# RTC_IC.net
KiCad netlist of a schematic drawn in Altium Designer
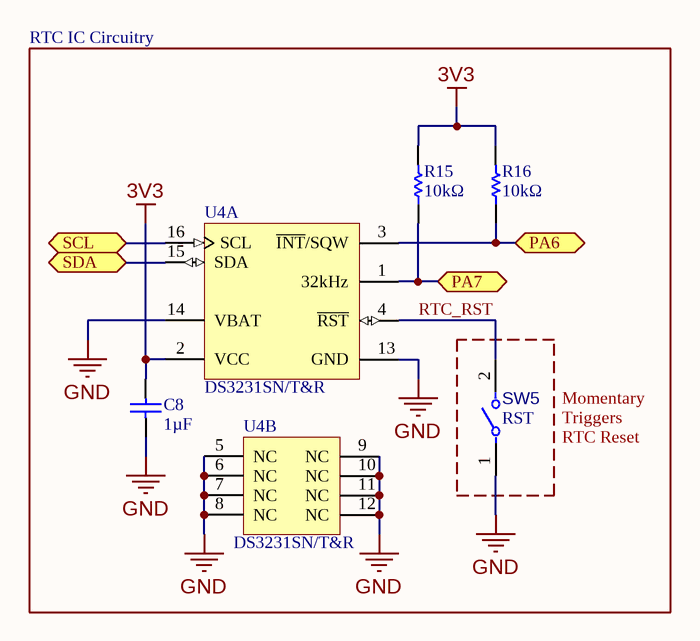
[diagram p0: RTC IC.SchDoc]

(export (version "E")
  (design (tool "Eeschema 10.0.6"))
  (components
    (comp (ref "C8")
      (value "1µF")
      (footprint "CAPC3216X110X50LL20T25")
      (description "Chip Capacitor, 1 uF, +/- 10%, 50 V, -55 to 125 degC, 1206 (3216 Metric), RoHS, Tape and Reel")
      (fields (field (name "MANUFACTURER") "Kemet") (field (name "TOLERANCE") "10%"))
      (libsource (lib "Altium Content Vault") (part "CAP-NP-2"))
    )
    (comp (ref "R15")
      (value "10kΩ")
      (footprint "RESC3116X65X40LL10T20")
      (description "Chip Resistor, 10 KOhm, +/- 1%, 0.25 W, -55 to 155 degC, 1206 (3216 Metric), RoHS, Tape and Reel")
      (fields (field (name "TOLERANCE") "1%") (field (name "MANUFACTURER") "Yageo"))
      (libsource (lib "Altium Content Vault") (part "RES-2"))
    )
    (comp (ref "R16")
      (value "10kΩ")
      (footprint "RESC3116X65X40LL10T20")
      (description "Chip Resistor, 10 KOhm, +/- 1%, 0.25 W, -55 to 155 degC, 1206 (3216 Metric), RoHS, Tape and Reel")
      (fields (field (name "TOLERANCE") "1%") (field (name "MANUFACTURER") "Yageo"))
      (libsource (lib "Altium Content Vault") (part "RES-2"))
    )
    (comp (ref "SW5")
      (value "RST")
      (footprint "FP-B3U-1000P-B-MFG")
      (description "SWITCH TACTILE SPST-NO 0.05A 12V")
      (fields
        (field (name "MANUFACTURER PART NUMBER") "B3U-1000P-B")
        (field (name "OCTOPART") "https://octopart.com/b3u-1000p-b-omron-1057356")
      )
      (libsource (lib "Altium Content Vault") (part "bb27bde45df87f1f469753f287ef5ae"))
    )
    (comp (ref "U4")
      (value "DS3231SN/T&R")
      (footprint "W16-H2_N")
      (description "Extremely Accurate I2C-Integrated Real-Time Clock/TCXO/Crystal, 16-Pin SO, -40 to 85 degC, Reel")
      (libsource (lib "Altium Content Vault") (part "MAX-RTC-16-DS3231S-W16#H2"))
    )
  )
  (nets
    (net (code "1") (name "/PA6") (class "Default")
      (node (ref "R16") (pin "1") (pinfunction "1_1") (pintype "passive"))
      (node (ref "U4") (pin "3") (pinfunction "~{INT}/SQW_3") (pintype "open_collector"))
    )
    (net (code "2") (name "/PA7") (class "Default")
      (node (ref "R15") (pin "1") (pinfunction "1_1") (pintype "passive"))
      (node (ref "U4") (pin "1") (pinfunction "32kHz_1") (pintype "open_collector"))
    )
    (net (code "3") (name "/RTC_RST") (class "Default")
      (node (ref "SW5") (pin "2") (pinfunction "2_2") (pintype "passive"))
      (node (ref "U4") (pin "4") (pinfunction "~{RST}_4") (pintype "bidirectional"))
    )
    (net (code "4") (name "/SCL") (class "Default")
      (node (ref "U4") (pin "16") (pinfunction "SCL_16") (pintype "input"))
    )
    (net (code "5") (name "/SDA") (class "Default")
      (node (ref "U4") (pin "15") (pinfunction "SDA_15") (pintype "bidirectional"))
    )
    (net (code "6") (name "3V3") (class "Default")
      (node (ref "C8") (pin "2") (pinfunction "2_2") (pintype "passive"))
      (node (ref "R15") (pin "2") (pinfunction "2_2") (pintype "passive"))
      (node (ref "R16") (pin "2") (pinfunction "2_2") (pintype "passive"))
      (node (ref "U4") (pin "2") (pinfunction "VCC_2") (pintype "power_in"))
    )
    (net (code "7") (name "GND") (class "Default")
      (node (ref "C8") (pin "1") (pinfunction "1_1") (pintype "passive"))
      (node (ref "SW5") (pin "1") (pinfunction "1_1") (pintype "passive"))
      (node (ref "U4") (pin "10") (pinfunction "NC_10") (pintype "passive"))
      (node (ref "U4") (pin "11") (pinfunction "NC_11") (pintype "passive"))
      (node (ref "U4") (pin "12") (pinfunction "NC_12") (pintype "passive"))
      (node (ref "U4") (pin "13") (pinfunction "GND_13") (pintype "power_in"))
      (node (ref "U4") (pin "14") (pinfunction "VBAT_14") (pintype "power_in"))
      (node (ref "U4") (pin "5") (pinfunction "NC_5") (pintype "passive"))
      (node (ref "U4") (pin "6") (pinfunction "NC_6") (pintype "passive"))
      (node (ref "U4") (pin "7") (pinfunction "NC_7") (pintype "passive"))
      (node (ref "U4") (pin "8") (pinfunction "NC_8") (pintype "passive"))
      (node (ref "U4") (pin "9") (pinfunction "NC_9") (pintype "passive"))
    )
  )
)
